# IPOD_LCD.net
KiCad netlist of a schematic drawn in Altium Designer
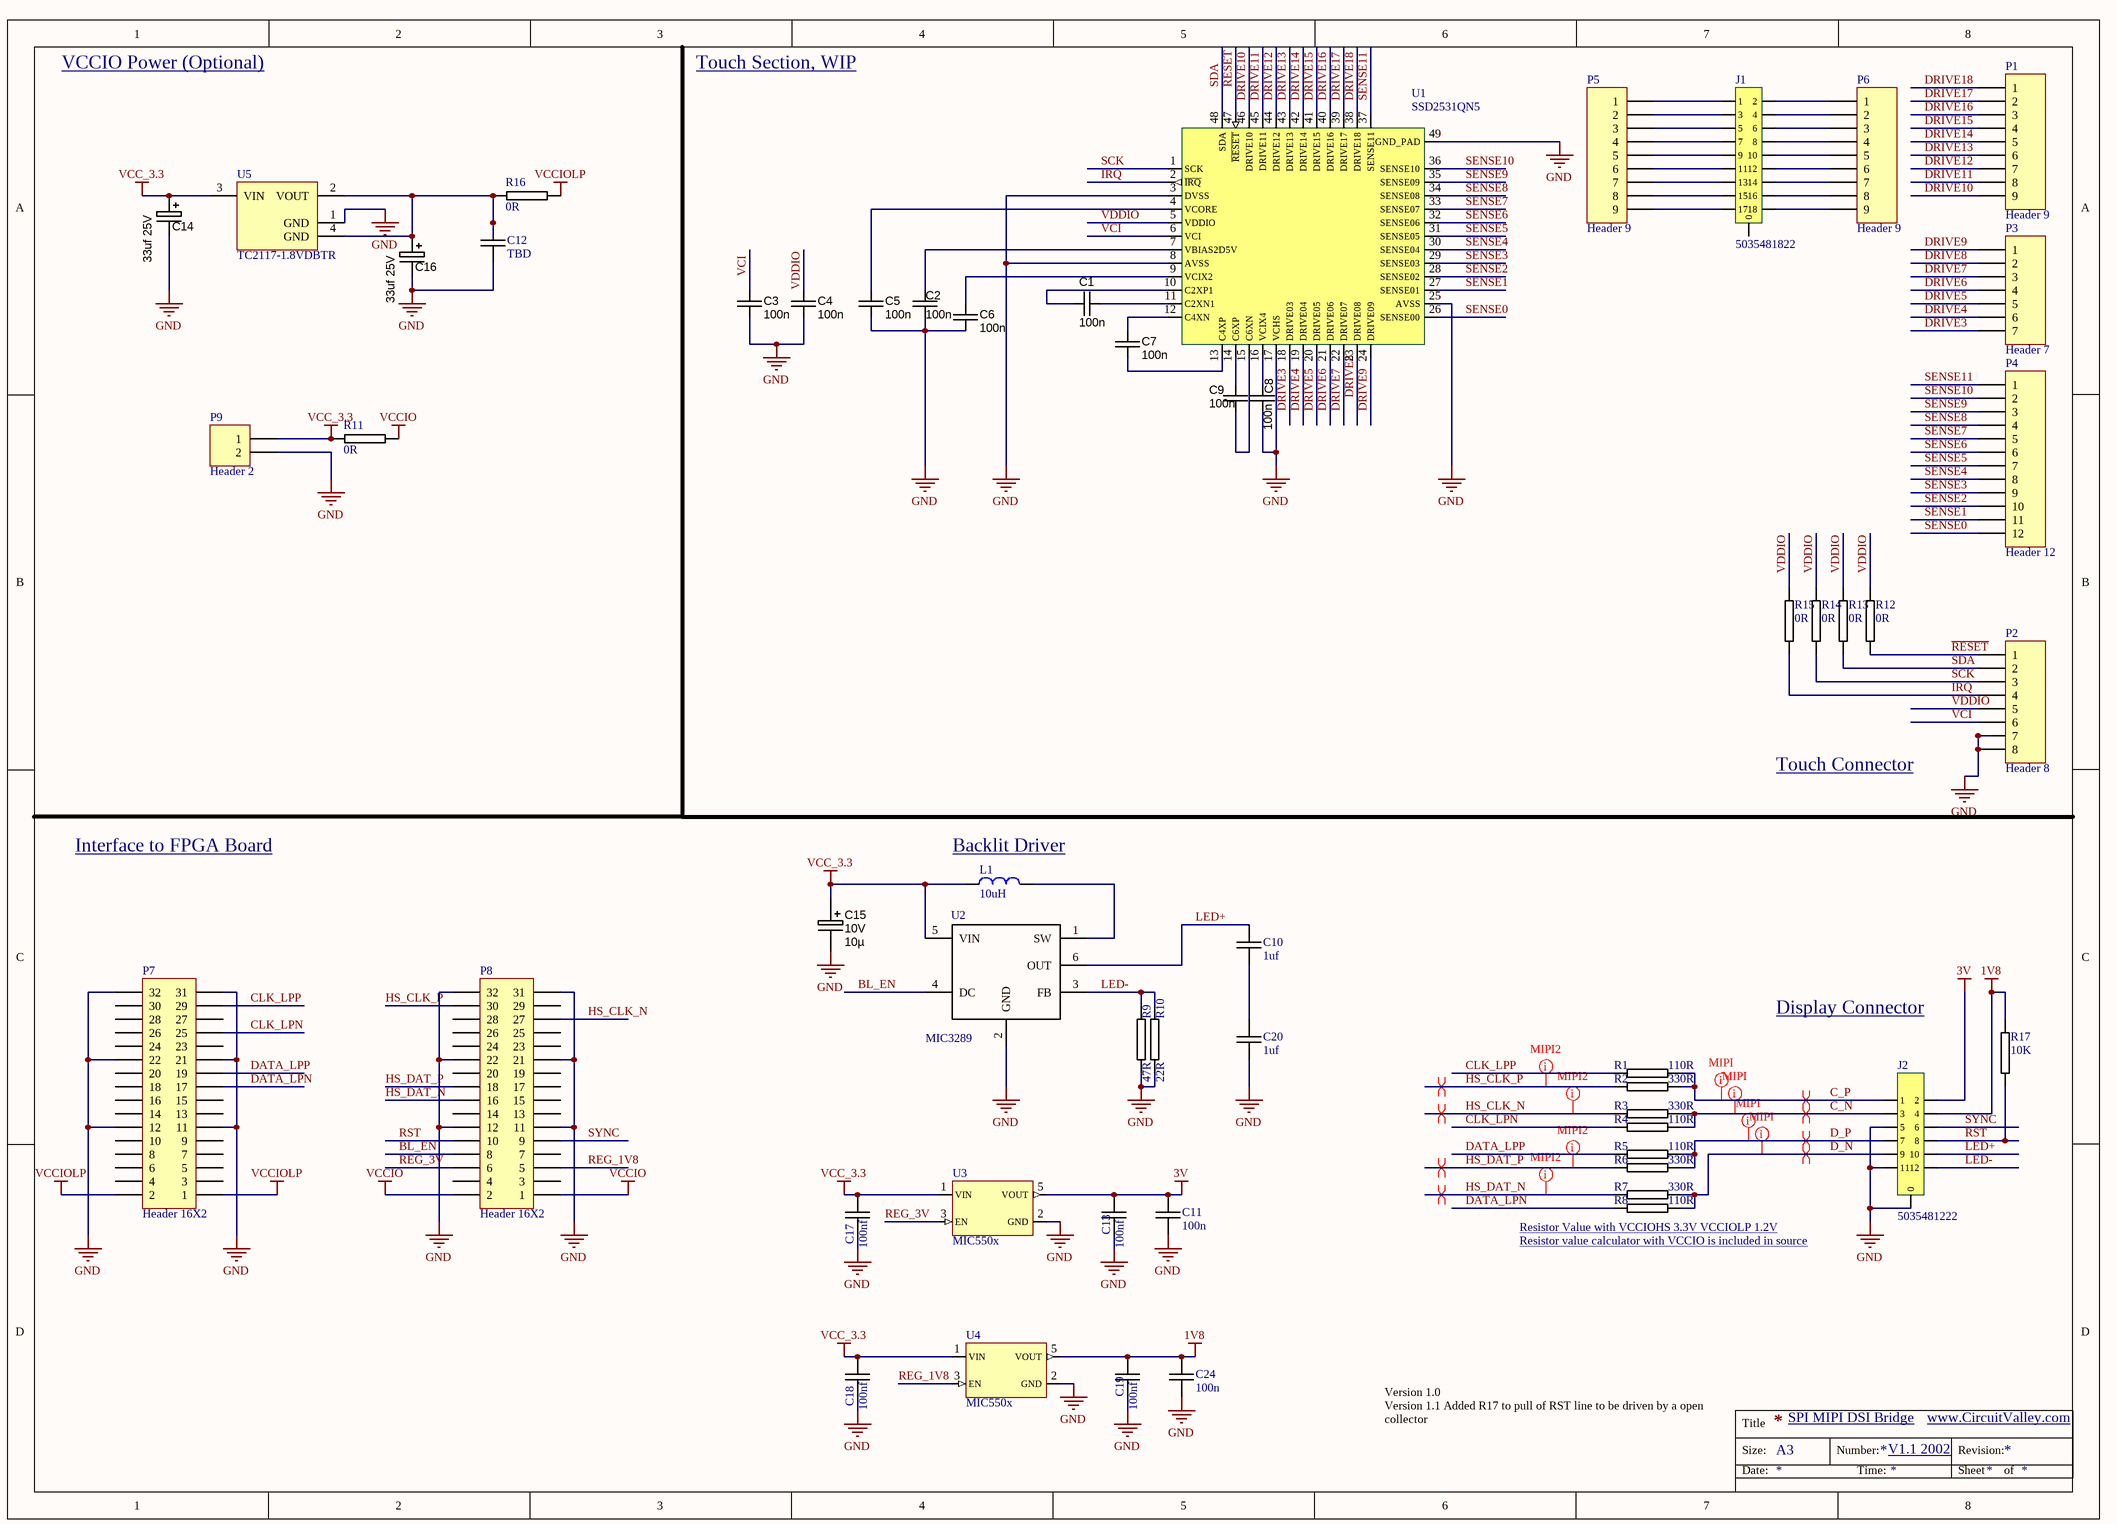
[diagram p0: IPOD_LCD.SchDoc]

(export (version "E")
  (design (tool "Eeschema 10.0.6"))
  (components
    (comp (ref "C1")
      (value "100n")
      (footprint "CAPC1608N")
      (description "Capacitor SMD Cer 10pF 5% 50V NP0 0603")
      (fields (field (name "TOLERANCE") "±5%") (field (name "PART") "C0603X104K5RAC"))
      (libsource (lib "PBL - Capacitors") (part "CAPC_10p_0603_NP0_1%_50V"))
    )
    (comp (ref "C2")
      (value "100n")
      (footprint "CAPC1608N")
      (description "Capacitor SMD Cer 10pF 5% 50V NP0 0603")
      (fields (field (name "TOLERANCE") "±5%") (field (name "PART") "C0603X104K5RAC"))
      (libsource (lib "PBL - Capacitors") (part "CAPC_10p_0603_NP0_1%_50V"))
    )
    (comp (ref "C3")
      (value "100n")
      (footprint "CAPC1608N")
      (description "Capacitor SMD Cer 10pF 5% 50V NP0 0603")
      (fields (field (name "TOLERANCE") "±5%") (field (name "PART") "C0603X104K5RAC"))
      (libsource (lib "PBL - Capacitors") (part "CAPC_10p_0603_NP0_1%_50V"))
    )
    (comp (ref "C4")
      (value "100n")
      (footprint "CAPC1608N")
      (description "Capacitor SMD Cer 10pF 5% 50V NP0 0603")
      (fields (field (name "TOLERANCE") "±5%") (field (name "PART") "C0603X104K5RAC"))
      (libsource (lib "PBL - Capacitors") (part "CAPC_10p_0603_NP0_1%_50V"))
    )
    (comp (ref "C5")
      (value "100n")
      (footprint "CAPC1608N")
      (description "Capacitor SMD Cer 10pF 5% 50V NP0 0603")
      (fields (field (name "TOLERANCE") "±5%") (field (name "PART") "C0603X104K5RAC"))
      (libsource (lib "PBL - Capacitors") (part "CAPC_10p_0603_NP0_1%_50V"))
    )
    (comp (ref "C6")
      (value "100n")
      (footprint "CAPC1608N")
      (description "Capacitor SMD Cer 10pF 5% 50V NP0 0603")
      (fields (field (name "TOLERANCE") "±5%") (field (name "PART") "C0603X104K5RAC"))
      (libsource (lib "PBL - Capacitors") (part "CAPC_10p_0603_NP0_1%_50V"))
    )
    (comp (ref "C7")
      (value "100n")
      (footprint "CAPC1608N")
      (description "Capacitor SMD Cer 10pF 5% 50V NP0 0603")
      (fields (field (name "TOLERANCE") "±5%") (field (name "PART") "C0603X104K5RAC"))
      (libsource (lib "PBL - Capacitors") (part "CAPC_10p_0603_NP0_1%_50V"))
    )
    (comp (ref "C8")
      (value "100n")
      (footprint "CAPC1608N")
      (description "Capacitor SMD Cer 10pF 5% 50V NP0 0603")
      (fields (field (name "TOLERANCE") "±5%") (field (name "PART") "C0603X104K5RAC"))
      (libsource (lib "PBL - Capacitors") (part "CAPC_10p_0603_NP0_1%_50V"))
    )
    (comp (ref "C9")
      (value "100n")
      (footprint "CAPC1608N")
      (description "Capacitor SMD Cer 10pF 5% 50V NP0 0603")
      (fields (field (name "TOLERANCE") "±5%") (field (name "PART") "C0603X104K5RAC"))
      (libsource (lib "PBL - Capacitors") (part "CAPC_10p_0603_NP0_1%_50V"))
    )
    (comp (ref "C10")
      (value "1uf")
      (footprint "0805C-TBD")
      (description "CAPACITOR 0805 CERAMIC VALUE TO BE DETERMINED")
      (libsource (lib "Generic") (part "0805C-TBD"))
    )
    (comp (ref "C11")
      (value "100n")
      (footprint "0805C-TBD")
      (description "CAPACITOR 0805 CERAMIC VALUE TO BE DETERMINED")
      (libsource (lib "Generic") (part "0805C-TBD"))
    )
    (comp (ref "C12")
      (value "TBD")
      (footprint "0805C-TBD")
      (description "CAPACITOR 0805 CERAMIC VALUE TO BE DETERMINED")
      (libsource (lib "Generic") (part "0805C-TBD"))
    )
    (comp (ref "C13")
      (value "100nf")
      (footprint "0603C-GENERIC")
      (description "CAPACITOR 0603 CERAMIC")
      (fields
        (field (name "MANUFACTURER") "Murata Electronics North America")
        (field (name "MANUFACTURER PART NUMBER") "GRM188R60J106ME47D")
      )
      (libsource (lib "Generic") (part "0603C-10UF-6V3-X5R-MUR"))
    )
    (comp (ref "C14")
      (value "33uf 25V")
      (footprint "CAPMP7343X310N")
      (description "Capacitor SMD Tant 330uF 20% 6V3 2917")
      (fields
        (field (name "TOLERANCE") "±20%")
        (field (name "MANUFACTURER PART NUMBER") "T520D337M006ATE015")
      )
      (libsource (lib "PBL - Capacitors") (part "CAPT_330u_2917_6V3"))
    )
    (comp (ref "C15")
      (value "10µ")
      (footprint "CAPMP3528X210N")
      (description "Capacitor SMD Tantalum 47uF 20% 6.3V 1210")
      (fields (field (name "TOLERANCE") "±20%") (field (name "RATINGS") "10V"))
      (libsource (lib "PBL - Capacitors") (part "CAPT_47u_1210_6V3"))
    )
    (comp (ref "C16")
      (value "33uf 25V")
      (footprint "CAPMP7343X310N")
      (description "Capacitor SMD Tant 330uF 20% 6V3 2917")
      (fields
        (field (name "TOLERANCE") "±20%")
        (field (name "MANUFACTURER PART NUMBER") "T520D337M006ATE015")
      )
      (libsource (lib "PBL - Capacitors") (part "CAPT_330u_2917_6V3"))
    )
    (comp (ref "C17")
      (value "100nf")
      (footprint "0603C-GENERIC")
      (description "CAPACITOR 0603 CERAMIC")
      (fields
        (field (name "MANUFACTURER") "Murata Electronics North America")
        (field (name "MANUFACTURER PART NUMBER") "GRM188R60J106ME47D")
      )
      (libsource (lib "Generic") (part "0603C-10UF-6V3-X5R-MUR"))
    )
    (comp (ref "C18")
      (value "100nf")
      (footprint "0603C-GENERIC")
      (description "CAPACITOR 0603 CERAMIC")
      (fields
        (field (name "MANUFACTURER") "Murata Electronics North America")
        (field (name "MANUFACTURER PART NUMBER") "GRM188R60J106ME47D")
      )
      (libsource (lib "Generic") (part "0603C-10UF-6V3-X5R-MUR"))
    )
    (comp (ref "C19")
      (value "100nf")
      (footprint "0603C-GENERIC")
      (description "CAPACITOR 0603 CERAMIC")
      (fields
        (field (name "MANUFACTURER") "Murata Electronics North America")
        (field (name "MANUFACTURER PART NUMBER") "GRM188R60J106ME47D")
      )
      (libsource (lib "Generic") (part "0603C-10UF-6V3-X5R-MUR"))
    )
    (comp (ref "C20")
      (value "1uf")
      (footprint "0805C-TBD")
      (description "CAPACITOR 0805 CERAMIC VALUE TO BE DETERMINED")
      (libsource (lib "Generic") (part "0805C-TBD"))
    )
    (comp (ref "C24")
      (value "100n")
      (footprint "0805C-TBD")
      (description "CAPACITOR 0805 CERAMIC VALUE TO BE DETERMINED")
      (libsource (lib "Generic") (part "0805C-TBD"))
    )
    (comp (ref "J1")
      (value "5035481822")
      (footprint "5035481822")
      (description "5035481822 18 Pin Ipod Touch")
      (libsource (lib "molex") (part "5035481822"))
    )
    (comp (ref "J2")
      (value "5035481222")
      (footprint "5035481222")
      (description "5035481222 12 Ipod lcd")
      (libsource (lib "molex") (part "5035481222"))
    )
    (comp (ref "L1")
      (value "10uH")
      (footprint "IFSC-1515AH-01")
      (libsource (lib "Inductor") (part "inductor_smd"))
    )
    (comp (ref "P1")
      (value "Header 9")
      (footprint "HDR1X9")
      (description "Header, 9-Pin")
      (fields (field (name "PUBLISHER") "Altium Limited"))
      (libsource (lib "Miscellaneous Connectors") (part "Header 9"))
    )
    (comp (ref "P2")
      (value "Header 8")
      (footprint "HDR1X8")
      (description "Header, 8-Pin")
      (fields (field (name "PUBLISHER") "Altium Limited"))
      (libsource (lib "Miscellaneous Connectors") (part "Header 8"))
    )
    (comp (ref "P3")
      (value "Header 7")
      (footprint "HDR1X7")
      (description "Header, 7-Pin")
      (fields (field (name "PUBLISHER") "Altium Limited"))
      (libsource (lib "Miscellaneous Connectors") (part "Header 7"))
    )
    (comp (ref "P4")
      (value "Header 12")
      (footprint "HDR1X12")
      (description "Header, 12-Pin")
      (fields (field (name "PUBLISHER") "Altium Limited"))
      (libsource (lib "Miscellaneous Connectors") (part "Header 12"))
    )
    (comp (ref "P5")
      (value "Header 9")
      (footprint "HDR1X9")
      (description "Header, 9-Pin")
      (fields (field (name "PUBLISHER") "Altium Limited"))
      (libsource (lib "") (part "Header 9_1"))
    )
    (comp (ref "P6")
      (value "Header 9")
      (footprint "HDR1X9")
      (description "Header, 9-Pin")
      (fields (field (name "PUBLISHER") "Altium Limited"))
      (libsource (lib "Miscellaneous Connectors") (part "Header 9"))
    )
    (comp (ref "P7")
      (value "Header 16X2")
      (footprint "HDR2X16")
      (description "Header, 16-Pin, Dual row")
      (fields (field (name "PUBLISHER") "Altium Limited"))
      (libsource (lib "Miscellaneous Connectors") (part "Header 16X2"))
    )
    (comp (ref "P8")
      (value "Header 16X2")
      (footprint "HDR2X16")
      (description "Header, 16-Pin, Dual row")
      (fields (field (name "PUBLISHER") "Altium Limited"))
      (libsource (lib "Miscellaneous Connectors") (part "Header 16X2"))
    )
    (comp (ref "P9")
      (value "Header 2")
      (footprint "HDR1X2")
      (description "Header, 2-Pin")
      (fields (field (name "PUBLISHER") "Altium Limited"))
      (libsource (lib "Miscellaneous Connectors") (part "Header 2"))
    )
    (comp (ref "R1")
      (value "110R")
      (footprint "0805R-GENERIC")
      (description "RESISTOR 0805 1 WATT")
      (libsource (lib "Generic") (part "0805R-0R"))
    )
    (comp (ref "R2")
      (value "330R")
      (footprint "0805R-GENERIC")
      (description "RESISTOR 0805 1 WATT")
      (libsource (lib "Generic") (part "0805R-0R"))
    )
    (comp (ref "R3")
      (value "330R")
      (footprint "0805R-GENERIC")
      (description "RESISTOR 0805 1 WATT")
      (libsource (lib "Generic") (part "0805R-0R"))
    )
    (comp (ref "R4")
      (value "110R")
      (footprint "0805R-GENERIC")
      (description "RESISTOR 0805 1 WATT")
      (libsource (lib "Generic") (part "0805R-0R"))
    )
    (comp (ref "R5")
      (value "110R")
      (footprint "0805R-GENERIC")
      (description "RESISTOR 0805 1 WATT")
      (libsource (lib "Generic") (part "0805R-0R"))
    )
    (comp (ref "R6")
      (value "330R")
      (footprint "0805R-GENERIC")
      (description "RESISTOR 0805 1 WATT")
      (libsource (lib "Generic") (part "0805R-0R"))
    )
    (comp (ref "R7")
      (value "330R")
      (footprint "0805R-GENERIC")
      (description "RESISTOR 0805 1 WATT")
      (libsource (lib "Generic") (part "0805R-0R"))
    )
    (comp (ref "R8")
      (value "110R")
      (footprint "0805R-GENERIC")
      (description "RESISTOR 0805 1 WATT")
      (libsource (lib "Generic") (part "0805R-0R"))
    )
    (comp (ref "R9")
      (value "47R")
      (footprint "0805R-GENERIC")
      (description "RESISTOR 0805 1 WATT")
      (libsource (lib "Generic") (part "0805R-0R"))
    )
    (comp (ref "R10")
      (value "22R")
      (footprint "0805R-GENERIC")
      (description "RESISTOR 0805 1 WATT")
      (libsource (lib "Generic") (part "0805R-0R"))
    )
    (comp (ref "R11")
      (value "0R")
      (footprint "0805R-GENERIC")
      (description "RESISTOR 0805 1 WATT")
      (libsource (lib "Generic") (part "0805R-0R"))
    )
    (comp (ref "R12")
      (value "0R")
      (footprint "0805R-GENERIC")
      (description "RESISTOR 0805 1 WATT")
      (libsource (lib "Generic") (part "0805R-0R"))
    )
    (comp (ref "R13")
      (value "0R")
      (footprint "0805R-GENERIC")
      (description "RESISTOR 0805 1 WATT")
      (libsource (lib "Generic") (part "0805R-0R"))
    )
    (comp (ref "R14")
      (value "0R")
      (footprint "0805R-GENERIC")
      (description "RESISTOR 0805 1 WATT")
      (libsource (lib "Generic") (part "0805R-0R"))
    )
    (comp (ref "R15")
      (value "0R")
      (footprint "0805R-GENERIC")
      (description "RESISTOR 0805 1 WATT")
      (libsource (lib "Generic") (part "0805R-0R"))
    )
    (comp (ref "R16")
      (value "0R")
      (footprint "0805R-GENERIC")
      (description "RESISTOR 0805 1 WATT")
      (libsource (lib "Generic") (part "0805R-0R"))
    )
    (comp (ref "R17")
      (value "10K")
      (footprint "0805R-GENERIC")
      (description "RESISTOR 0805 1 WATT")
      (libsource (lib "Generic") (part "0805R-0R"))
    )
    (comp (ref "U1")
      (value "SSD2531QN5")
      (footprint "QFN48_6x6_0.4")
      (libsource (lib "Solomentech") (part "SSD2531QN5"))
    )
    (comp (ref "U2") (value "MIC3289") (footprint "SOT23-6") (libsource (lib "Generic") (part "MIC3289")))
    (comp (ref "U3") (value "MIC550x") (footprint "SOT23-5") (libsource (lib "cvlib") (part "MIC550x")))
    (comp (ref "U4") (value "MIC550x") (footprint "SOT23-5") (libsource (lib "cvlib") (part "MIC550x")))
    (comp (ref "U5")
      (value "TC2117-1.8VDBTR")
      (footprint "SOT-223-DB3_N")
      (description "800 mA Fixed Low Dropout Positive Regulator, 3-Pin SOT-223, Extended Temperature, Tape and Reel")
      (fields (field (name "PUBLISHER") "Altium Limited"))
      (libsource (lib "Microchip Power Mgt Line Regulator") (part "TC2117-1.8VDBTR"))
    )
  )
  (nets
    (net (code "1") (name "/BL_EN") (class "Default")
      (node (ref "P8") (pin "8") (pinfunction "8_8") (pintype "passive"))
      (node (ref "U2") (pin "4") (pinfunction "DC_4") (pintype "passive"))
    )
    (net (code "2") (name "/CLK_LPN") (class "Default")
      (node (ref "P7") (pin "25") (pinfunction "25_25") (pintype "passive"))
      (node (ref "R4") (pin "1") (pintype "passive"))
    )
    (net (code "3") (name "/CLK_LPP") (class "Default")
      (node (ref "P7") (pin "29") (pinfunction "29_29") (pintype "passive"))
      (node (ref "R1") (pin "1") (pintype "passive"))
    )
    (net (code "4") (name "/C_N") (class "Default")
      (node (ref "J2") (pin "3") (pinfunction "3_3") (pintype "passive"))
      (node (ref "R3") (pin "2") (pintype "passive"))
      (node (ref "R4") (pin "2") (pintype "passive"))
    )
    (net (code "5") (name "/C_P") (class "Default")
      (node (ref "J2") (pin "1") (pinfunction "1_1") (pintype "passive"))
      (node (ref "R1") (pin "2") (pintype "passive"))
      (node (ref "R2") (pin "2") (pintype "passive"))
    )
    (net (code "6") (name "/DATA_LPN") (class "Default")
      (node (ref "P7") (pin "17") (pinfunction "17_17") (pintype "passive"))
      (node (ref "R8") (pin "1") (pintype "passive"))
    )
    (net (code "7") (name "/DATA_LPP") (class "Default")
      (node (ref "P7") (pin "19") (pinfunction "19_19") (pintype "passive"))
      (node (ref "R5") (pin "1") (pintype "passive"))
    )
    (net (code "8") (name "/DRIVE3") (class "Default")
      (node (ref "P3") (pin "7") (pinfunction "7_7") (pintype "passive"))
      (node (ref "U1") (pin "18") (pinfunction "DRIVE03_18") (pintype "passive"))
    )
    (net (code "9") (name "/DRIVE4") (class "Default")
      (node (ref "P3") (pin "6") (pinfunction "6_6") (pintype "passive"))
      (node (ref "U1") (pin "19") (pinfunction "DRIVE04_19") (pintype "passive"))
    )
    (net (code "10") (name "/DRIVE5") (class "Default")
      (node (ref "P3") (pin "5") (pinfunction "5_5") (pintype "passive"))
      (node (ref "U1") (pin "20") (pinfunction "DRIVE05_20") (pintype "passive"))
    )
    (net (code "11") (name "/DRIVE6") (class "Default")
      (node (ref "P3") (pin "4") (pinfunction "4_4") (pintype "passive"))
      (node (ref "U1") (pin "21") (pinfunction "DRIVE06_21") (pintype "passive"))
    )
    (net (code "12") (name "/DRIVE7") (class "Default")
      (node (ref "P3") (pin "3") (pinfunction "3_3") (pintype "passive"))
      (node (ref "U1") (pin "22") (pinfunction "DRIVE07_22") (pintype "passive"))
    )
    (net (code "13") (name "/DRIVE8") (class "Default")
      (node (ref "P3") (pin "2") (pinfunction "2_2") (pintype "passive"))
      (node (ref "U1") (pin "23") (pinfunction "DRIVE08_23") (pintype "passive"))
    )
    (net (code "14") (name "/DRIVE9") (class "Default")
      (node (ref "P3") (pin "1") (pinfunction "1_1") (pintype "passive"))
      (node (ref "U1") (pin "24") (pinfunction "DRIVE09_24") (pintype "passive"))
    )
    (net (code "15") (name "/DRIVE10") (class "Default")
      (node (ref "P1") (pin "9") (pinfunction "9_9") (pintype "passive"))
      (node (ref "U1") (pin "46") (pinfunction "DRIVE10_46") (pintype "passive"))
    )
    (net (code "16") (name "/DRIVE11") (class "Default")
      (node (ref "P1") (pin "8") (pinfunction "8_8") (pintype "passive"))
      (node (ref "U1") (pin "45") (pinfunction "DRIVE11_45") (pintype "passive"))
    )
    (net (code "17") (name "/DRIVE12") (class "Default")
      (node (ref "P1") (pin "7") (pinfunction "7_7") (pintype "passive"))
      (node (ref "U1") (pin "44") (pinfunction "DRIVE12_44") (pintype "passive"))
    )
    (net (code "18") (name "/DRIVE13") (class "Default")
      (node (ref "P1") (pin "6") (pinfunction "6_6") (pintype "passive"))
      (node (ref "U1") (pin "43") (pinfunction "DRIVE13_43") (pintype "passive"))
    )
    (net (code "19") (name "/DRIVE14") (class "Default")
      (node (ref "P1") (pin "5") (pinfunction "5_5") (pintype "passive"))
      (node (ref "U1") (pin "42") (pinfunction "DRIVE14_42") (pintype "passive"))
    )
    (net (code "20") (name "/DRIVE15") (class "Default")
      (node (ref "P1") (pin "4") (pinfunction "4_4") (pintype "passive"))
      (node (ref "U1") (pin "41") (pinfunction "DRIVE15_41") (pintype "passive"))
    )
    (net (code "21") (name "/DRIVE16") (class "Default")
      (node (ref "P1") (pin "3") (pinfunction "3_3") (pintype "passive"))
      (node (ref "U1") (pin "40") (pinfunction "DRIVE16_40") (pintype "passive"))
    )
    (net (code "22") (name "/DRIVE17") (class "Default")
      (node (ref "P1") (pin "2") (pinfunction "2_2") (pintype "passive"))
      (node (ref "U1") (pin "39") (pinfunction "DRIVE17_39") (pintype "passive"))
    )
    (net (code "23") (name "/DRIVE18") (class "Default")
      (node (ref "P1") (pin "1") (pinfunction "1_1") (pintype "passive"))
      (node (ref "U1") (pin "38") (pinfunction "DRIVE18_38") (pintype "passive"))
    )
    (net (code "24") (name "/D_N") (class "Default")
      (node (ref "J2") (pin "9") (pinfunction "9_9") (pintype "passive"))
      (node (ref "R7") (pin "2") (pintype "passive"))
      (node (ref "R8") (pin "2") (pintype "passive"))
    )
    (net (code "25") (name "/D_P") (class "Default")
      (node (ref "J2") (pin "7") (pinfunction "7_7") (pintype "passive"))
      (node (ref "R5") (pin "2") (pintype "passive"))
      (node (ref "R6") (pin "2") (pintype "passive"))
    )
    (net (code "26") (name "/HS_CLK_N") (class "Default")
      (node (ref "P8") (pin "27") (pinfunction "27_27") (pintype "passive"))
      (node (ref "R3") (pin "1") (pintype "passive"))
    )
    (net (code "27") (name "/HS_CLK_P") (class "Default")
      (node (ref "P8") (pin "30") (pinfunction "30_30") (pintype "passive"))
      (node (ref "R2") (pin "1") (pintype "passive"))
    )
    (net (code "28") (name "/HS_DAT_N") (class "Default")
      (node (ref "P8") (pin "16") (pinfunction "16_16") (pintype "passive"))
      (node (ref "R7") (pin "1") (pintype "passive"))
    )
    (net (code "29") (name "/HS_DAT_P") (class "Default")
      (node (ref "P8") (pin "18") (pinfunction "18_18") (pintype "passive"))
      (node (ref "R6") (pin "1") (pintype "passive"))
    )
    (net (code "30") (name "/LED+") (class "Default")
      (node (ref "C10") (pin "1") (pintype "passive"))
      (node (ref "J2") (pin "10") (pinfunction "10_10") (pintype "passive"))
      (node (ref "U2") (pin "6") (pinfunction "OUT_6") (pintype "passive"))
    )
    (net (code "31") (name "/LED-") (class "Default")
      (node (ref "J2") (pin "12") (pinfunction "12_12") (pintype "passive"))
      (node (ref "R10") (pin "2") (pintype "passive"))
      (node (ref "R9") (pin "2") (pintype "passive"))
      (node (ref "U2") (pin "3") (pinfunction "FB_3") (pintype "passive"))
    )
    (net (code "32") (name "/REG_1V8") (class "Default")
      (node (ref "P8") (pin "5") (pinfunction "5_5") (pintype "passive"))
      (node (ref "U4") (pin "3") (pinfunction "EN_3") (pintype "input"))
    )
    (net (code "33") (name "/REG_3V") (class "Default")
      (node (ref "P8") (pin "6") (pinfunction "6_6") (pintype "passive"))
      (node (ref "U3") (pin "3") (pinfunction "EN_3") (pintype "input"))
    )
    (net (code "34") (name "/RST") (class "Default")
      (node (ref "J2") (pin "8") (pinfunction "8_8") (pintype "passive"))
      (node (ref "P8") (pin "10") (pinfunction "10_10") (pintype "passive"))
      (node (ref "R17") (pin "1") (pintype "passive"))
    )
    (net (code "35") (name "/SCK") (class "Default")
      (node (ref "P2") (pin "3") (pinfunction "3_3") (pintype "passive"))
      (node (ref "R14") (pin "1") (pintype "passive"))
      (node (ref "U1") (pin "1") (pinfunction "SCK_1") (pintype "passive"))
    )
    (net (code "36") (name "/SDA") (class "Default")
      (node (ref "P2") (pin "2") (pinfunction "2_2") (pintype "passive"))
      (node (ref "R13") (pin "1") (pintype "passive"))
      (node (ref "U1") (pin "48") (pinfunction "SDA_48") (pintype "passive"))
    )
    (net (code "37") (name "/SENSE0") (class "Default")
      (node (ref "P4") (pin "12") (pinfunction "12_12") (pintype "passive"))
      (node (ref "U1") (pin "26") (pinfunction "SENSE00_26") (pintype "passive"))
    )
    (net (code "38") (name "/SENSE1") (class "Default")
      (node (ref "P4") (pin "11") (pinfunction "11_11") (pintype "passive"))
      (node (ref "U1") (pin "27") (pinfunction "SENSE01_27") (pintype "passive"))
    )
    (net (code "39") (name "/SENSE2") (class "Default")
      (node (ref "P4") (pin "10") (pinfunction "10_10") (pintype "passive"))
      (node (ref "U1") (pin "28") (pinfunction "SENSE02_28") (pintype "passive"))
    )
    (net (code "40") (name "/SENSE3") (class "Default")
      (node (ref "P4") (pin "9") (pinfunction "9_9") (pintype "passive"))
      (node (ref "U1") (pin "29") (pinfunction "SENSE03_29") (pintype "passive"))
    )
    (net (code "41") (name "/SENSE4") (class "Default")
      (node (ref "P4") (pin "8") (pinfunction "8_8") (pintype "passive"))
      (node (ref "U1") (pin "30") (pinfunction "SENSE04_30") (pintype "passive"))
    )
    (net (code "42") (name "/SENSE5") (class "Default")
      (node (ref "P4") (pin "7") (pinfunction "7_7") (pintype "passive"))
      (node (ref "U1") (pin "31") (pinfunction "SENSE05_31") (pintype "passive"))
    )
    (net (code "43") (name "/SENSE6") (class "Default")
      (node (ref "P4") (pin "6") (pinfunction "6_6") (pintype "passive"))
      (node (ref "U1") (pin "32") (pinfunction "SENSE06_32") (pintype "passive"))
    )
    (net (code "44") (name "/SENSE7") (class "Default")
      (node (ref "P4") (pin "5") (pinfunction "5_5") (pintype "passive"))
      (node (ref "U1") (pin "33") (pinfunction "SENSE07_33") (pintype "passive"))
    )
    (net (code "45") (name "/SENSE8") (class "Default")
      (node (ref "P4") (pin "4") (pinfunction "4_4") (pintype "passive"))
      (node (ref "U1") (pin "34") (pinfunction "SENSE08_34") (pintype "passive"))
    )
    (net (code "46") (name "/SENSE9") (class "Default")
      (node (ref "P4") (pin "3") (pinfunction "3_3") (pintype "passive"))
      (node (ref "U1") (pin "35") (pinfunction "SENSE09_35") (pintype "passive"))
    )
    (net (code "47") (name "/SENSE10") (class "Default")
      (node (ref "P4") (pin "2") (pinfunction "2_2") (pintype "passive"))
      (node (ref "U1") (pin "36") (pinfunction "SENSE10_36") (pintype "passive"))
    )
    (net (code "48") (name "/SENSE11") (class "Default")
      (node (ref "P4") (pin "1") (pinfunction "1_1") (pintype "passive"))
      (node (ref "U1") (pin "37") (pinfunction "SENSE11_37") (pintype "passive"))
    )
    (net (code "49") (name "/SYNC") (class "Default")
      (node (ref "J2") (pin "6") (pinfunction "6_6") (pintype "passive"))
      (node (ref "P8") (pin "9") (pinfunction "9_9") (pintype "passive"))
    )
    (net (code "50") (name "/VCI") (class "Default")
      (node (ref "C3") (pin "1") (pintype "passive"))
      (node (ref "P2") (pin "6") (pinfunction "6_6") (pintype "passive"))
      (node (ref "U1") (pin "6") (pinfunction "VCI_6") (pintype "power_in"))
    )
    (net (code "51") (name "/VDDIO") (class "Default")
      (node (ref "C4") (pin "1") (pintype "passive"))
      (node (ref "P2") (pin "5") (pinfunction "5_5") (pintype "passive"))
      (node (ref "R12") (pin "2") (pintype "passive"))
      (node (ref "R13") (pin "2") (pintype "passive"))
      (node (ref "R14") (pin "2") (pintype "passive"))
      (node (ref "R15") (pin "2") (pintype "passive"))
      (node (ref "U1") (pin "5") (pinfunction "VDDIO_5") (pintype "power_in"))
    )
    (net (code "52") (name "/~{IRQ}") (class "Default")
      (node (ref "P2") (pin "4") (pinfunction "4_4") (pintype "passive"))
      (node (ref "R15") (pin "1") (pintype "passive"))
      (node (ref "U1") (pin "2") (pinfunction "~{IRQ}_2") (pintype "output"))
    )
    (net (code "53") (name "/~{RESET}") (class "Default")
      (node (ref "P2") (pin "1") (pinfunction "1_1") (pintype "passive"))
      (node (ref "R12") (pin "1") (pintype "passive"))
      (node (ref "U1") (pin "47") (pinfunction "~{RESET}_47") (pintype "input"))
    )
    (net (code "54") (name "1V8") (class "Default")
      (node (ref "C19") (pin "2") (pintype "passive"))
      (node (ref "C24") (pin "1") (pintype "passive"))
      (node (ref "J2") (pin "4") (pinfunction "4_4") (pintype "passive"))
      (node (ref "R17") (pin "2") (pintype "passive"))
      (node (ref "U4") (pin "5") (pinfunction "VOUT_5") (pintype "output"))
    )
    (net (code "55") (name "3V") (class "Default")
      (node (ref "C11") (pin "1") (pintype "passive"))
      (node (ref "C13") (pin "2") (pintype "passive"))
      (node (ref "J2") (pin "2") (pinfunction "2_2") (pintype "passive"))
      (node (ref "U3") (pin "5") (pinfunction "VOUT_5") (pintype "output"))
    )
    (net (code "56") (name "GND") (class "Default")
      (node (ref "C11") (pin "2") (pintype "passive"))
      (node (ref "C12") (pin "2") (pintype "passive"))
      (node (ref "C13") (pin "1") (pintype "passive"))
      (node (ref "C14") (pin "2") (pintype "passive"))
      (node (ref "C15") (pin "2") (pintype "passive"))
      (node (ref "C16") (pin "2") (pintype "passive"))
      (node (ref "C17") (pin "1") (pintype "passive"))
      (node (ref "C18") (pin "1") (pintype "passive"))
      (node (ref "C19") (pin "1") (pintype "passive"))
      (node (ref "C2") (pin "2") (pintype "passive"))
      (node (ref "C20") (pin "2") (pintype "passive"))
      (node (ref "C24") (pin "2") (pintype "passive"))
      (node (ref "C3") (pin "2") (pintype "passive"))
      (node (ref "C4") (pin "2") (pintype "passive"))
      (node (ref "C5") (pin "2") (pintype "passive"))
      (node (ref "C6") (pin "2") (pintype "passive"))
      (node (ref "C8") (pin "2") (pintype "passive"))
      (node (ref "J2") (pin "0") (pinfunction "0_0") (pintype "passive"))
      (node (ref "J2") (pin "11") (pinfunction "11_11") (pintype "passive"))
      (node (ref "J2") (pin "5") (pinfunction "5_5") (pintype "passive"))
      (node (ref "P2") (pin "7") (pinfunction "7_7") (pintype "passive"))
      (node (ref "P2") (pin "8") (pinfunction "8_8") (pintype "passive"))
      (node (ref "P7") (pin "11") (pinfunction "11_11") (pintype "passive"))
      (node (ref "P7") (pin "12") (pinfunction "12_12") (pintype "passive"))
      (node (ref "P7") (pin "21") (pinfunction "21_21") (pintype "passive"))
      (node (ref "P7") (pin "22") (pinfunction "22_22") (pintype "passive"))
      (node (ref "P7") (pin "31") (pinfunction "31_31") (pintype "passive"))
      (node (ref "P7") (pin "32") (pinfunction "32_32") (pintype "passive"))
      (node (ref "P8") (pin "11") (pinfunction "11_11") (pintype "passive"))
      (node (ref "P8") (pin "12") (pinfunction "12_12") (pintype "passive"))
      (node (ref "P8") (pin "21") (pinfunction "21_21") (pintype "passive"))
      (node (ref "P8") (pin "22") (pinfunction "22_22") (pintype "passive"))
      (node (ref "P8") (pin "31") (pinfunction "31_31") (pintype "passive"))
      (node (ref "P8") (pin "32") (pinfunction "32_32") (pintype "passive"))
      (node (ref "P9") (pin "2") (pinfunction "2_2") (pintype "passive"))
      (node (ref "R10") (pin "1") (pintype "passive"))
      (node (ref "R9") (pin "1") (pintype "passive"))
      (node (ref "U1") (pin "17") (pinfunction "VCHS_17") (pintype "passive"))
      (node (ref "U1") (pin "25") (pinfunction "AVSS_25") (pintype "power_in"))
      (node (ref "U1") (pin "3") (pinfunction "DVSS_3") (pintype "power_in"))
      (node (ref "U1") (pin "49") (pinfunction "GND_PAD_49") (pintype "passive"))
      (node (ref "U1") (pin "8") (pinfunction "AVSS_8") (pintype "power_in"))
      (node (ref "U2") (pin "2") (pinfunction "GND_2") (pintype "passive"))
      (node (ref "U3") (pin "2") (pinfunction "GND_2") (pintype "power_in"))
      (node (ref "U4") (pin "2") (pinfunction "GND_2") (pintype "power_in"))
      (node (ref "U5") (pin "1") (pinfunction "GND_1") (pintype "power_in"))
    )
    (net (code "57") (name "Net-(C10-Pad2)") (class "Default")
      (node (ref "C10") (pin "2") (pintype "passive"))
      (node (ref "C20") (pin "1") (pintype "passive"))
    )
    (net (code "58") (name "Net-(J1-Pad1)") (class "Default")
      (node (ref "J1") (pin "1") (pinfunction "1_1") (pintype "passive"))
      (node (ref "P5") (pin "1") (pinfunction "1_1") (pintype "passive"))
    )
    (net (code "59") (name "Net-(J1-Pad2)") (class "Default")
      (node (ref "J1") (pin "2") (pinfunction "2_2") (pintype "passive"))
      (node (ref "P6") (pin "1") (pinfunction "1_1") (pintype "passive"))
    )
    (net (code "60") (name "Net-(J1-Pad3)") (class "Default")
      (node (ref "J1") (pin "3") (pinfunction "3_3") (pintype "passive"))
      (node (ref "P5") (pin "2") (pinfunction "2_2") (pintype "passive"))
    )
    (net (code "61") (name "Net-(J1-Pad4)") (class "Default")
      (node (ref "J1") (pin "4") (pinfunction "4_4") (pintype "passive"))
      (node (ref "P6") (pin "2") (pinfunction "2_2") (pintype "passive"))
    )
    (net (code "62") (name "Net-(J1-Pad5)") (class "Default")
      (node (ref "J1") (pin "5") (pinfunction "5_5") (pintype "passive"))
      (node (ref "P5") (pin "3") (pinfunction "3_3") (pintype "passive"))
    )
    (net (code "63") (name "Net-(J1-Pad6)") (class "Default")
      (node (ref "J1") (pin "6") (pinfunction "6_6") (pintype "passive"))
      (node (ref "P6") (pin "3") (pinfunction "3_3") (pintype "passive"))
    )
    (net (code "64") (name "Net-(J1-Pad7)") (class "Default")
      (node (ref "J1") (pin "7") (pinfunction "7_7") (pintype "passive"))
      (node (ref "P5") (pin "4") (pinfunction "4_4") (pintype "passive"))
    )
    (net (code "65") (name "Net-(J1-Pad8)") (class "Default")
      (node (ref "J1") (pin "8") (pinfunction "8_8") (pintype "passive"))
      (node (ref "P6") (pin "4") (pinfunction "4_4") (pintype "passive"))
    )
    (net (code "66") (name "Net-(J1-Pad9)") (class "Default")
      (node (ref "J1") (pin "9") (pinfunction "9_9") (pintype "passive"))
      (node (ref "P5") (pin "5") (pinfunction "5_5") (pintype "passive"))
    )
    (net (code "67") (name "Net-(J1-Pad10)") (class "Default")
      (node (ref "J1") (pin "10") (pinfunction "10_10") (pintype "passive"))
      (node (ref "P6") (pin "5") (pinfunction "5_5") (pintype "passive"))
    )
    (net (code "68") (name "Net-(J1-Pad11)") (class "Default")
      (node (ref "J1") (pin "11") (pinfunction "11_11") (pintype "passive"))
      (node (ref "P5") (pin "6") (pinfunction "6_6") (pintype "passive"))
    )
    (net (code "69") (name "Net-(J1-Pad12)") (class "Default")
      (node (ref "J1") (pin "12") (pinfunction "12_12") (pintype "passive"))
      (node (ref "P6") (pin "6") (pinfunction "6_6") (pintype "passive"))
    )
    (net (code "70") (name "Net-(J1-Pad13)") (class "Default")
      (node (ref "J1") (pin "13") (pinfunction "13_13") (pintype "passive"))
      (node (ref "P5") (pin "7") (pinfunction "7_7") (pintype "passive"))
    )
    (net (code "71") (name "Net-(J1-Pad14)") (class "Default")
      (node (ref "J1") (pin "14") (pinfunction "14_14") (pintype "passive"))
      (node (ref "P6") (pin "7") (pinfunction "7_7") (pintype "passive"))
    )
    (net (code "72") (name "Net-(J1-Pad15)") (class "Default")
      (node (ref "J1") (pin "15") (pinfunction "15_15") (pintype "passive"))
      (node (ref "P5") (pin "8") (pinfunction "8_8") (pintype "passive"))
    )
    (net (code "73") (name "Net-(J1-Pad16)") (class "Default")
      (node (ref "J1") (pin "16") (pinfunction "16_16") (pintype "passive"))
      (node (ref "P6") (pin "8") (pinfunction "8_8") (pintype "passive"))
    )
    (net (code "74") (name "Net-(J1-Pad17)") (class "Default")
      (node (ref "J1") (pin "17") (pinfunction "17_17") (pintype "passive"))
      (node (ref "P5") (pin "9") (pinfunction "9_9") (pintype "passive"))
    )
    (net (code "75") (name "Net-(J1-Pad18)") (class "Default")
      (node (ref "J1") (pin "18") (pinfunction "18_18") (pintype "passive"))
      (node (ref "P6") (pin "9") (pinfunction "9_9") (pintype "passive"))
    )
    (net (code "76") (name "Net-(U1-C2XN1)") (class "Default")
      (node (ref "C1") (pin "1") (pintype "passive"))
      (node (ref "U1") (pin "11") (pinfunction "C2XN1_11") (pintype "passive"))
    )
    (net (code "77") (name "Net-(U1-C2XP1)") (class "Default")
      (node (ref "C1") (pin "2") (pintype "passive"))
      (node (ref "U1") (pin "10") (pinfunction "C2XP1_10") (pintype "passive"))
    )
    (net (code "78") (name "Net-(U1-C4XN)") (class "Default")
      (node (ref "C7") (pin "1") (pintype "passive"))
      (node (ref "U1") (pin "12") (pinfunction "C4XN_12") (pintype "passive"))
    )
    (net (code "79") (name "Net-(U1-C4XP)") (class "Default")
      (node (ref "C7") (pin "2") (pintype "passive"))
      (node (ref "U1") (pin "13") (pinfunction "C4XP_13") (pintype "passive"))
    )
    (net (code "80") (name "Net-(U1-C6XN)") (class "Default")
      (node (ref "C9") (pin "2") (pintype "passive"))
      (node (ref "U1") (pin "15") (pinfunction "C6XN_15") (pintype "passive"))
    )
    (net (code "81") (name "Net-(U1-C6XP)") (class "Default")
      (node (ref "C9") (pin "1") (pintype "passive"))
      (node (ref "U1") (pin "14") (pinfunction "C6XP_14") (pintype "passive"))
    )
    (net (code "82") (name "Net-(U1-VBIAS2D5V)") (class "Default")
      (node (ref "C2") (pin "1") (pintype "passive"))
      (node (ref "U1") (pin "7") (pinfunction "VBIAS2D5V_7") (pintype "power_in"))
    )
    (net (code "83") (name "Net-(U1-VCIX2)") (class "Default")
      (node (ref "C6") (pin "1") (pintype "passive"))
      (node (ref "U1") (pin "9") (pinfunction "VCIX2_9") (pintype "power_in"))
    )
    (net (code "84") (name "Net-(U1-VCIX4)") (class "Default")
      (node (ref "C8") (pin "1") (pintype "passive"))
      (node (ref "U1") (pin "16") (pinfunction "VCIX4_16") (pintype "passive"))
    )
    (net (code "85") (name "Net-(U1-VCORE)") (class "Default")
      (node (ref "C5") (pin "1") (pintype "passive"))
      (node (ref "U1") (pin "4") (pinfunction "VCORE_4") (pintype "power_in"))
    )
    (net (code "86") (name "Net-(U2-SW)") (class "Default")
      (node (ref "L1") (pin "2") (pinfunction "2_2") (pintype "passive"))
      (node (ref "U2") (pin "1") (pinfunction "SW_1") (pintype "passive"))
    )
    (net (code "87") (name "Net-(U5-VOUT)") (class "Default")
      (node (ref "C12") (pin "1") (pintype "passive"))
      (node (ref "C16") (pin "1") (pintype "passive"))
      (node (ref "R16") (pin "2") (pintype "passive"))
      (node (ref "U5") (pin "2") (pinfunction "VOUT_2") (pintype "power_in"))
      (node (ref "U5") (pin "4") (pinfunction "GND_4") (pintype "power_in"))
    )
    (net (code "88") (name "VCCIO") (class "Default")
      (node (ref "P8") (pin "1") (pinfunction "1_1") (pintype "passive"))
      (node (ref "P8") (pin "2") (pinfunction "2_2") (pintype "passive"))
      (node (ref "R11") (pin "2") (pintype "passive"))
    )
    (net (code "89") (name "VCCIOLP") (class "Default")
      (node (ref "P7") (pin "1") (pinfunction "1_1") (pintype "passive"))
      (node (ref "P7") (pin "2") (pinfunction "2_2") (pintype "passive"))
      (node (ref "R16") (pin "1") (pintype "passive"))
    )
    (net (code "90") (name "VCC_3.3") (class "Default")
      (node (ref "C14") (pin "1") (pintype "passive"))
      (node (ref "C15") (pin "1") (pintype "passive"))
      (node (ref "C17") (pin "2") (pintype "passive"))
      (node (ref "C18") (pin "2") (pintype "passive"))
      (node (ref "L1") (pin "1") (pinfunction "1_1") (pintype "passive"))
      (node (ref "P9") (pin "1") (pinfunction "1_1") (pintype "passive"))
      (node (ref "R11") (pin "1") (pintype "passive"))
      (node (ref "U2") (pin "5") (pinfunction "VIN_5") (pintype "passive"))
      (node (ref "U3") (pin "1") (pinfunction "VIN_1") (pintype "power_in"))
      (node (ref "U4") (pin "1") (pinfunction "VIN_1") (pintype "power_in"))
      (node (ref "U5") (pin "3") (pinfunction "VIN_3") (pintype "power_in"))
    )
    (net (code "91") (name "unconnected-(J1-0-Pad19)") (class "Default")
      (node (ref "J1") (pin "19") (pinfunction "0_19") (pintype "passive"))
    )
    (net (code "92") (name "unconnected-(P7-Pad3)") (class "Default")
      (node (ref "P7") (pin "3") (pinfunction "3_3") (pintype "passive"))
    )
    (net (code "93") (name "unconnected-(P7-Pad4)") (class "Default")
      (node (ref "P7") (pin "4") (pinfunction "4_4") (pintype "passive"))
    )
    (net (code "94") (name "unconnected-(P7-Pad5)") (class "Default")
      (node (ref "P7") (pin "5") (pinfunction "5_5") (pintype "passive"))
    )
    (net (code "95") (name "unconnected-(P7-Pad6)") (class "Default")
      (node (ref "P7") (pin "6") (pinfunction "6_6") (pintype "passive"))
    )
    (net (code "96") (name "unconnected-(P7-Pad7)") (class "Default")
      (node (ref "P7") (pin "7") (pinfunction "7_7") (pintype "passive"))
    )
    (net (code "97") (name "unconnected-(P7-Pad8)") (class "Default")
      (node (ref "P7") (pin "8") (pinfunction "8_8") (pintype "passive"))
    )
    (net (code "98") (name "unconnected-(P7-Pad9)") (class "Default")
      (node (ref "P7") (pin "9") (pinfunction "9_9") (pintype "passive"))
    )
    (net (code "99") (name "unconnected-(P7-Pad10)") (class "Default")
      (node (ref "P7") (pin "10") (pinfunction "10_10") (pintype "passive"))
    )
    (net (code "100") (name "unconnected-(P7-Pad13)") (class "Default")
      (node (ref "P7") (pin "13") (pinfunction "13_13") (pintype "passive"))
    )
    (net (code "101") (name "unconnected-(P7-Pad14)") (class "Default")
      (node (ref "P7") (pin "14") (pinfunction "14_14") (pintype "passive"))
    )
    (net (code "102") (name "unconnected-(P7-Pad15)") (class "Default")
      (node (ref "P7") (pin "15") (pinfunction "15_15") (pintype "passive"))
    )
    (net (code "103") (name "unconnected-(P7-Pad16)") (class "Default")
      (node (ref "P7") (pin "16") (pinfunction "16_16") (pintype "passive"))
    )
    (net (code "104") (name "unconnected-(P7-Pad18)") (class "Default")
      (node (ref "P7") (pin "18") (pinfunction "18_18") (pintype "passive"))
    )
    (net (code "105") (name "unconnected-(P7-Pad20)") (class "Default")
      (node (ref "P7") (pin "20") (pinfunction "20_20") (pintype "passive"))
    )
    (net (code "106") (name "unconnected-(P7-Pad23)") (class "Default")
      (node (ref "P7") (pin "23") (pinfunction "23_23") (pintype "passive"))
    )
    (net (code "107") (name "unconnected-(P7-Pad24)") (class "Default")
      (node (ref "P7") (pin "24") (pinfunction "24_24") (pintype "passive"))
    )
    (net (code "108") (name "unconnected-(P7-Pad26)") (class "Default")
      (node (ref "P7") (pin "26") (pinfunction "26_26") (pintype "passive"))
    )
    (net (code "109") (name "unconnected-(P7-Pad27)") (class "Default")
      (node (ref "P7") (pin "27") (pinfunction "27_27") (pintype "passive"))
    )
    (net (code "110") (name "unconnected-(P7-Pad28)") (class "Default")
      (node (ref "P7") (pin "28") (pinfunction "28_28") (pintype "passive"))
    )
    (net (code "111") (name "unconnected-(P7-Pad30)") (class "Default")
      (node (ref "P7") (pin "30") (pinfunction "30_30") (pintype "passive"))
    )
    (net (code "112") (name "unconnected-(P8-Pad3)") (class "Default")
      (node (ref "P8") (pin "3") (pinfunction "3_3") (pintype "passive"))
    )
    (net (code "113") (name "unconnected-(P8-Pad4)") (class "Default")
      (node (ref "P8") (pin "4") (pinfunction "4_4") (pintype "passive"))
    )
    (net (code "114") (name "unconnected-(P8-Pad7)") (class "Default")
      (node (ref "P8") (pin "7") (pinfunction "7_7") (pintype "passive"))
    )
    (net (code "115") (name "unconnected-(P8-Pad13)") (class "Default")
      (node (ref "P8") (pin "13") (pinfunction "13_13") (pintype "passive"))
    )
    (net (code "116") (name "unconnected-(P8-Pad14)") (class "Default")
      (node (ref "P8") (pin "14") (pinfunction "14_14") (pintype "passive"))
    )
    (net (code "117") (name "unconnected-(P8-Pad15)") (class "Default")
      (node (ref "P8") (pin "15") (pinfunction "15_15") (pintype "passive"))
    )
    (net (code "118") (name "unconnected-(P8-Pad17)") (class "Default")
      (node (ref "P8") (pin "17") (pinfunction "17_17") (pintype "passive"))
    )
    (net (code "119") (name "unconnected-(P8-Pad19)") (class "Default")
      (node (ref "P8") (pin "19") (pinfunction "19_19") (pintype "passive"))
    )
    (net (code "120") (name "unconnected-(P8-Pad20)") (class "Default")
      (node (ref "P8") (pin "20") (pinfunction "20_20") (pintype "passive"))
    )
    (net (code "121") (name "unconnected-(P8-Pad23)") (class "Default")
      (node (ref "P8") (pin "23") (pinfunction "23_23") (pintype "passive"))
    )
    (net (code "122") (name "unconnected-(P8-Pad24)") (class "Default")
      (node (ref "P8") (pin "24") (pinfunction "24_24") (pintype "passive"))
    )
    (net (code "123") (name "unconnected-(P8-Pad25)") (class "Default")
      (node (ref "P8") (pin "25") (pinfunction "25_25") (pintype "passive"))
    )
    (net (code "124") (name "unconnected-(P8-Pad26)") (class "Default")
      (node (ref "P8") (pin "26") (pinfunction "26_26") (pintype "passive"))
    )
    (net (code "125") (name "unconnected-(P8-Pad28)") (class "Default")
      (node (ref "P8") (pin "28") (pinfunction "28_28") (pintype "passive"))
    )
    (net (code "126") (name "unconnected-(P8-Pad29)") (class "Default")
      (node (ref "P8") (pin "29") (pinfunction "29_29") (pintype "passive"))
    )
  )
)
